# design.net
KiCad netlist of a schematic drawn in Altium Designer
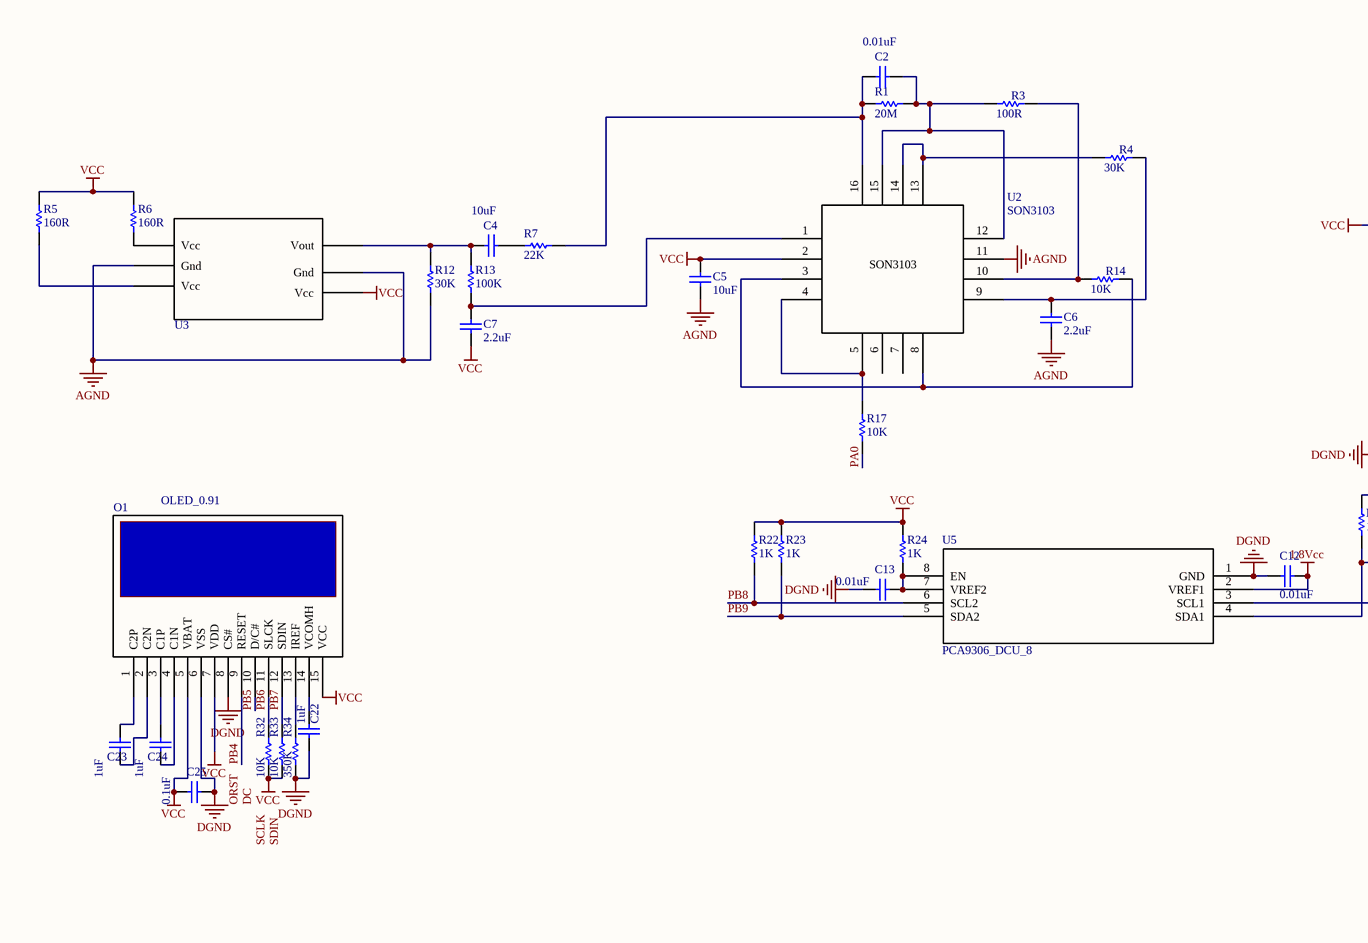
[diagram p0: 手环.SchDoc, left]
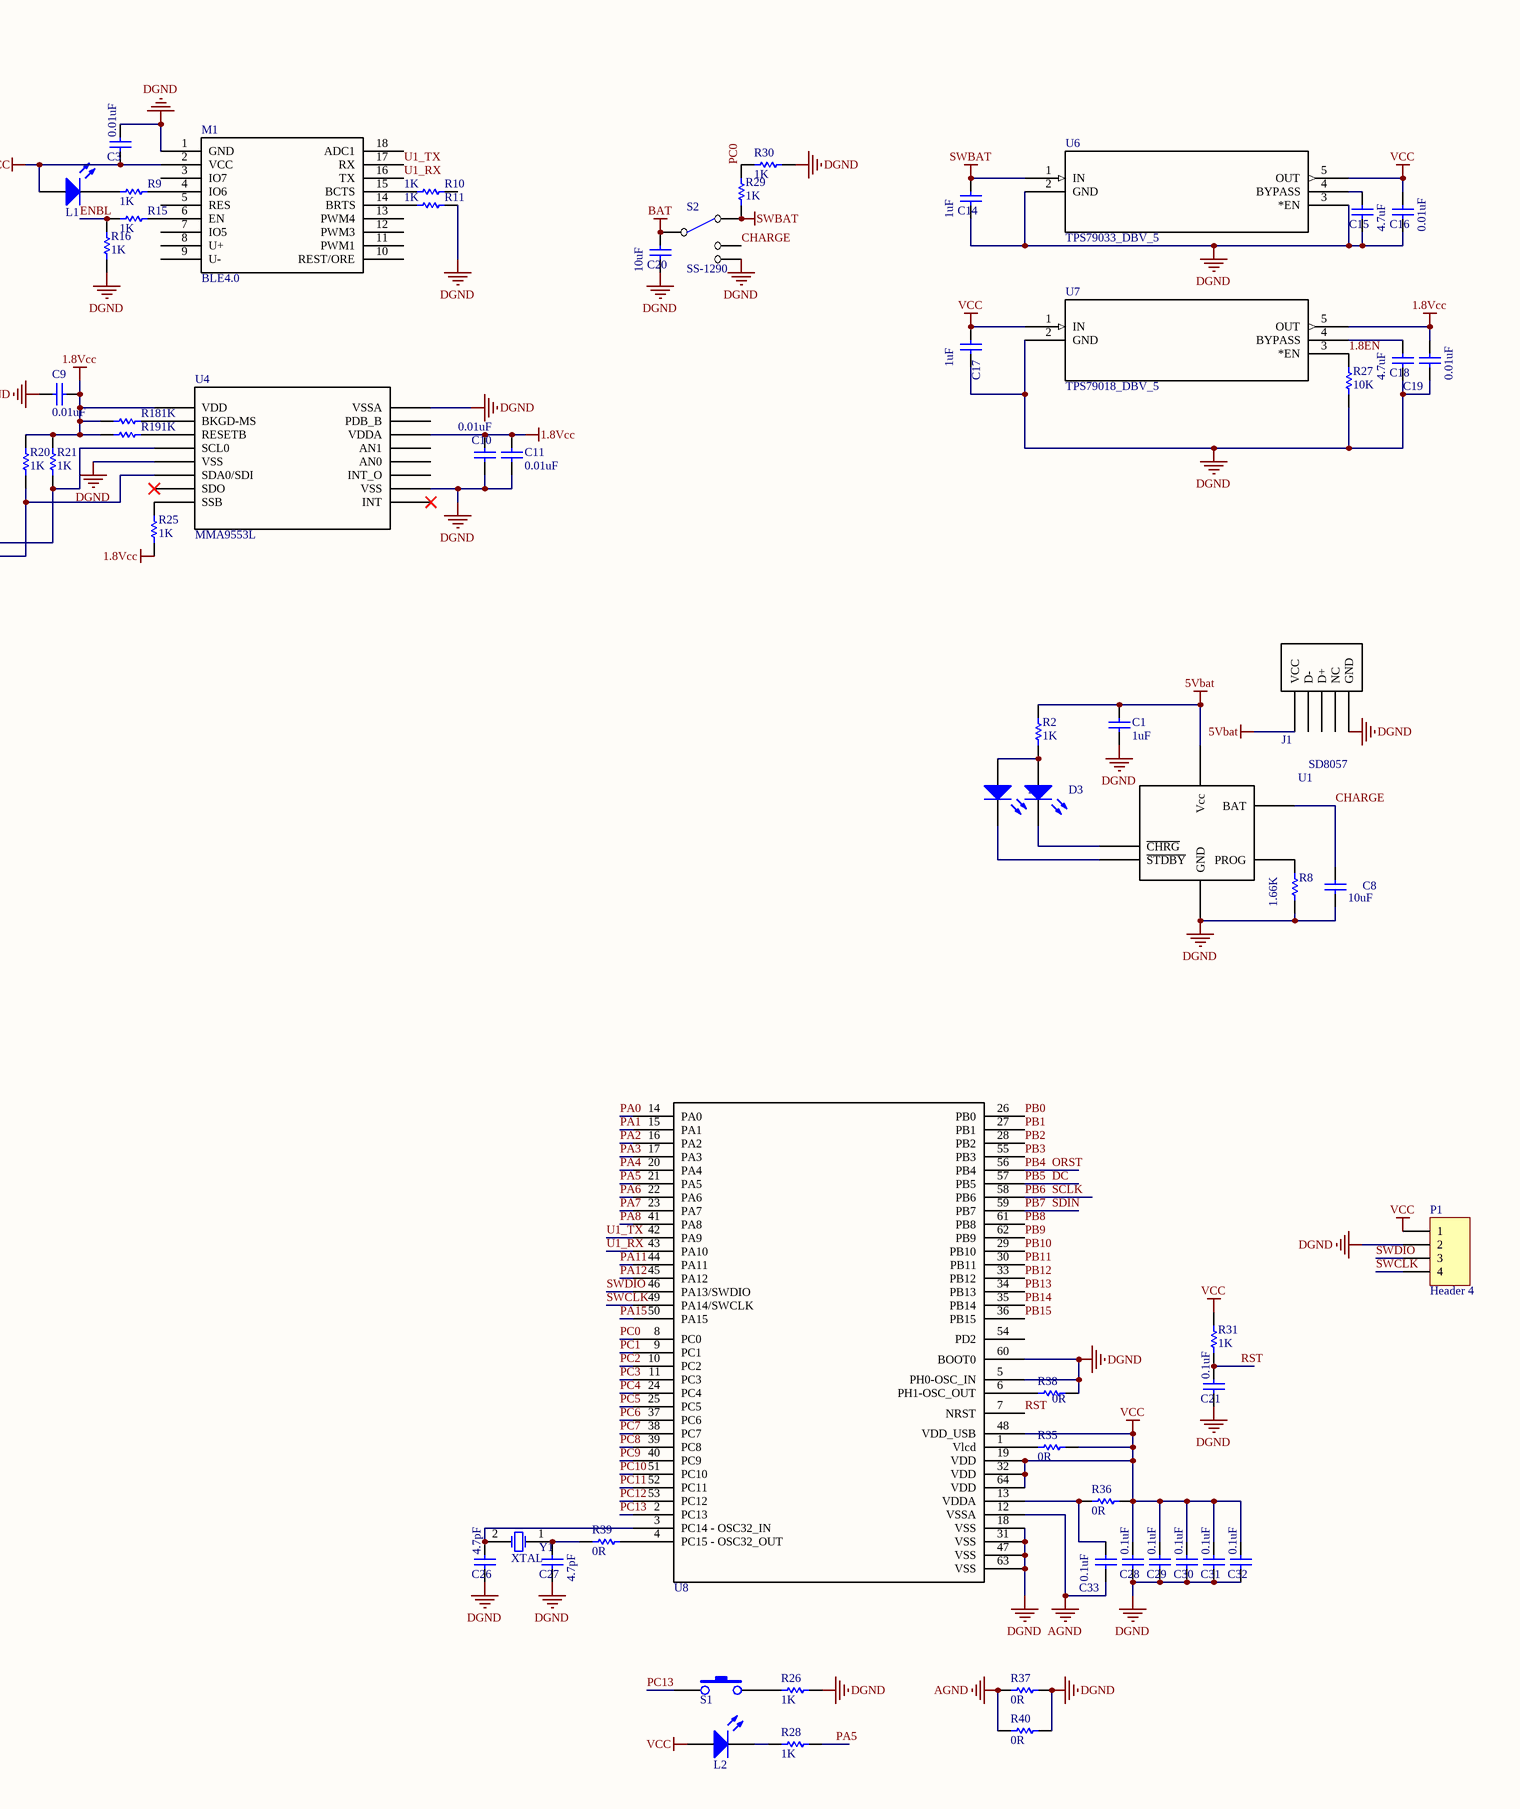
[diagram p1: 手环.SchDoc, right]

(export (version "E")
  (design (tool "Eeschema 10.0.6"))
  (components
    (comp (ref "C1")
      (value "1uF")
      (footprint "0603-C-SMD")
      (description "Capacitor")
      (fields (field (name "Comment") "Cap") (field (name "PUBLISHER") "Altium Limited"))
      (libsource (lib "Miscellaneous Devices") (part "Cap"))
    )
    (comp (ref "C2")
      (value "0.01uF")
      (footprint "0603-c-smd")
      (description "Capacitor")
      (fields (field (name "Comment") "Cap") (field (name "PUBLISHER") "Altium Limited"))
      (libsource (lib "Miscellaneous Devices") (part "Cap"))
    )
    (comp (ref "C3")
      (value "0.01uF")
      (footprint "RAD-0.3")
      (description "Capacitor")
      (fields (field (name "Comment") "Cap") (field (name "PUBLISHER") "Altium Limited"))
      (libsource (lib "Miscellaneous Devices") (part "Cap"))
    )
    (comp (ref "C4")
      (value "10uF")
      (footprint "0603-c-smd")
      (description "Capacitor")
      (fields (field (name "Comment") "Cap") (field (name "PUBLISHER") "Altium Limited"))
      (libsource (lib "Miscellaneous Devices") (part "Cap"))
    )
    (comp (ref "C5")
      (value "10uF")
      (footprint "0603-c-smd")
      (description "Capacitor")
      (fields (field (name "Comment") "Cap") (field (name "PUBLISHER") "Altium Limited"))
      (libsource (lib "Miscellaneous Devices") (part "Cap"))
    )
    (comp (ref "C6")
      (value "2.2uF")
      (footprint "0603-c-smd")
      (description "Capacitor")
      (fields (field (name "Comment") "Cap") (field (name "PUBLISHER") "Altium Limited"))
      (libsource (lib "Miscellaneous Devices") (part "Cap"))
    )
    (comp (ref "C7")
      (value "2.2uF")
      (footprint "0603-c-smd")
      (description "Capacitor")
      (fields (field (name "Comment") "Cap") (field (name "PUBLISHER") "Altium Limited"))
      (libsource (lib "Miscellaneous Devices") (part "Cap"))
    )
    (comp (ref "C8")
      (value "10uF")
      (footprint "0603-C-SMD")
      (description "Capacitor")
      (fields (field (name "Comment") "Cap") (field (name "PUBLISHER") "Altium Limited"))
      (libsource (lib "Miscellaneous Devices") (part "Cap"))
    )
    (comp (ref "C9")
      (value "0.01uF")
      (footprint "RAD-0.3")
      (description "Capacitor")
      (fields (field (name "Comment") "Cap") (field (name "PUBLISHER") "Altium Limited"))
      (libsource (lib "Miscellaneous Devices") (part "Cap"))
    )
    (comp (ref "C10")
      (value "0.01uF")
      (footprint "RAD-0.3")
      (description "Capacitor")
      (fields (field (name "Comment") "Cap") (field (name "PUBLISHER") "Altium Limited"))
      (libsource (lib "Miscellaneous Devices") (part "Cap"))
    )
    (comp (ref "C11")
      (value "0.01uF")
      (footprint "RAD-0.3")
      (description "Capacitor")
      (fields (field (name "Comment") "Cap") (field (name "PUBLISHER") "Altium Limited"))
      (libsource (lib "Miscellaneous Devices") (part "Cap"))
    )
    (comp (ref "C12")
      (value "0.01uF")
      (footprint "RAD-0.3")
      (description "Capacitor")
      (fields (field (name "Comment") "Cap") (field (name "PUBLISHER") "Altium Limited"))
      (libsource (lib "Miscellaneous Devices") (part "Cap"))
    )
    (comp (ref "C13")
      (value "0.01uF")
      (footprint "RAD-0.3")
      (description "Capacitor")
      (fields (field (name "Comment") "Cap") (field (name "PUBLISHER") "Altium Limited"))
      (libsource (lib "Miscellaneous Devices") (part "Cap"))
    )
    (comp (ref "C14")
      (value "1uF")
      (footprint "RAD-0.3")
      (description "Capacitor")
      (fields (field (name "Comment") "Cap") (field (name "PUBLISHER") "Altium Limited"))
      (libsource (lib "Miscellaneous Devices") (part "Cap"))
    )
    (comp (ref "C15")
      (value "4.7uF")
      (footprint "RAD-0.3")
      (description "Capacitor")
      (fields (field (name "Comment") "Cap") (field (name "PUBLISHER") "Altium Limited"))
      (libsource (lib "Miscellaneous Devices") (part "Cap"))
    )
    (comp (ref "C16")
      (value "0.01uF")
      (footprint "RAD-0.3")
      (description "Capacitor")
      (fields (field (name "Comment") "Cap") (field (name "PUBLISHER") "Altium Limited"))
      (libsource (lib "Miscellaneous Devices") (part "Cap"))
    )
    (comp (ref "C17")
      (value "1uF")
      (footprint "RAD-0.3")
      (description "Capacitor")
      (fields (field (name "Comment") "Cap") (field (name "PUBLISHER") "Altium Limited"))
      (libsource (lib "Miscellaneous Devices") (part "Cap"))
    )
    (comp (ref "C18")
      (value "4.7uF")
      (footprint "RAD-0.3")
      (description "Capacitor")
      (fields (field (name "Comment") "Cap") (field (name "PUBLISHER") "Altium Limited"))
      (libsource (lib "Miscellaneous Devices") (part "Cap"))
    )
    (comp (ref "C19")
      (value "0.01uF")
      (footprint "RAD-0.3")
      (description "Capacitor")
      (fields (field (name "Comment") "Cap") (field (name "PUBLISHER") "Altium Limited"))
      (libsource (lib "Miscellaneous Devices") (part "Cap"))
    )
    (comp (ref "C20")
      (value "10uF")
      (footprint "RAD-0.3")
      (description "Capacitor")
      (fields (field (name "Comment") "Cap") (field (name "PUBLISHER") "Altium Limited"))
      (libsource (lib "Miscellaneous Devices") (part "Cap"))
    )
    (comp (ref "C21")
      (value "0.1uF")
      (footprint "RAD-0.3")
      (description "Capacitor")
      (fields (field (name "Comment") "Cap") (field (name "PUBLISHER") "Altium Limited"))
      (libsource (lib "Miscellaneous Devices") (part "Cap"))
    )
    (comp (ref "C22")
      (value "1uF")
      (footprint "RAD-0.3")
      (description "Capacitor")
      (fields (field (name "Comment") "Cap") (field (name "PUBLISHER") "Altium Limited"))
      (libsource (lib "Miscellaneous Devices") (part "Cap"))
    )
    (comp (ref "C23")
      (value "1uF")
      (footprint "RAD-0.3")
      (description "Capacitor")
      (fields (field (name "Comment") "Cap") (field (name "PUBLISHER") "Altium Limited"))
      (libsource (lib "Miscellaneous Devices") (part "Cap"))
    )
    (comp (ref "C24")
      (value "1uF")
      (footprint "RAD-0.3")
      (description "Capacitor")
      (fields (field (name "Comment") "Cap") (field (name "PUBLISHER") "Altium Limited"))
      (libsource (lib "Miscellaneous Devices") (part "Cap"))
    )
    (comp (ref "C25")
      (value "0.1uF")
      (footprint "RAD-0.3")
      (description "Capacitor")
      (fields (field (name "Comment") "Cap") (field (name "PUBLISHER") "Altium Limited"))
      (libsource (lib "Miscellaneous Devices") (part "Cap"))
    )
    (comp (ref "C26")
      (value "4.7pF")
      (footprint "RAD-0.3")
      (description "Capacitor")
      (fields (field (name "Comment") "Cap") (field (name "PUBLISHER") "Altium Limited"))
      (libsource (lib "Miscellaneous Devices") (part "Cap"))
    )
    (comp (ref "C27")
      (value "4.7pF")
      (footprint "RAD-0.3")
      (description "Capacitor")
      (fields (field (name "Comment") "Cap") (field (name "PUBLISHER") "Altium Limited"))
      (libsource (lib "Miscellaneous Devices") (part "Cap"))
    )
    (comp (ref "C28")
      (value "0.1uF")
      (footprint "RAD-0.3")
      (description "Capacitor")
      (fields (field (name "Comment") "Cap") (field (name "PUBLISHER") "Altium Limited"))
      (libsource (lib "Miscellaneous Devices") (part "Cap"))
    )
    (comp (ref "C29")
      (value "0.1uF")
      (footprint "RAD-0.3")
      (description "Capacitor")
      (fields (field (name "Comment") "Cap") (field (name "PUBLISHER") "Altium Limited"))
      (libsource (lib "Miscellaneous Devices") (part "Cap"))
    )
    (comp (ref "C30")
      (value "0.1uF")
      (footprint "RAD-0.3")
      (description "Capacitor")
      (fields (field (name "Comment") "Cap") (field (name "PUBLISHER") "Altium Limited"))
      (libsource (lib "Miscellaneous Devices") (part "Cap"))
    )
    (comp (ref "C31")
      (value "0.1uF")
      (footprint "RAD-0.3")
      (description "Capacitor")
      (fields (field (name "Comment") "Cap") (field (name "PUBLISHER") "Altium Limited"))
      (libsource (lib "Miscellaneous Devices") (part "Cap"))
    )
    (comp (ref "C32")
      (value "0.1uF")
      (footprint "RAD-0.3")
      (description "Capacitor")
      (fields (field (name "Comment") "Cap") (field (name "PUBLISHER") "Altium Limited"))
      (libsource (lib "Miscellaneous Devices") (part "Cap"))
    )
    (comp (ref "C33")
      (value "0.1uF")
      (footprint "RAD-0.3")
      (description "Capacitor")
      (fields (field (name "Comment") "Cap") (field (name "PUBLISHER") "Altium Limited"))
      (libsource (lib "Miscellaneous Devices") (part "Cap"))
    )
    (comp (ref "D2")
      (value "LED0")
      (footprint "LED-0805")
      (description "Typical INFRARED GaAs LED")
      (fields (field (name "PUBLISHER") "Altium Limited"))
      (libsource (lib "Miscellaneous Devices") (part "LED0"))
    )
    (comp (ref "D3")
      (value "LED0")
      (footprint "LED-0805")
      (description "Typical INFRARED GaAs LED")
      (fields (field (name "PUBLISHER") "Altium Limited"))
      (libsource (lib "Miscellaneous Devices") (part "LED0"))
    )
    (comp (ref "J1") (value "USB") (footprint "Micro_USB") (libsource (lib "My Library") (part "micro usb")))
    (comp (ref "L1") (value "LED") (footprint "C2012") (libsource (lib "Sparks") (part "LED")))
    (comp (ref "L2") (value "LED") (footprint "C2012") (libsource (lib "Sparks") (part "LED")))
    (comp (ref "M1") (value "BLE4.0") (footprint "BLE4.0") (libsource (lib "My Library") (part "BLE4.0模块")))
    (comp (ref "O1")
      (value "OLED_0.91")
      (footprint "OLED_0.91")
      (libsource (lib "My Library") (part "OLED-0.91"))
    )
    (comp (ref "P1")
      (value "Header 4")
      (footprint "HDR1X4")
      (description "Header, 4-Pin")
      (fields (field (name "PUBLISHER") "Altium Limited"))
      (libsource (lib "Sparks") (part "Header 4"))
    )
    (comp (ref "R1")
      (value "20M")
      (footprint "R2012")
      (description "贴片电阻")
      (fields (field (name "Comment") "Res") (field (name "PUBLISHER") "Altium Limited"))
      (libsource (lib "Sparks") (part "Res"))
    )
    (comp (ref "R2")
      (value "1K")
      (footprint "0603-R-SMD")
      (description "贴片电阻")
      (fields (field (name "Comment") "Res") (field (name "PUBLISHER") "Altium Limited"))
      (libsource (lib "Sparks") (part "Res"))
    )
    (comp (ref "R3")
      (value "100R")
      (footprint "R2012")
      (description "贴片电阻")
      (fields (field (name "Comment") "Res") (field (name "PUBLISHER") "Altium Limited"))
      (libsource (lib "Sparks") (part "Res"))
    )
    (comp (ref "R4")
      (value "30K")
      (footprint "R2012")
      (description "贴片电阻")
      (fields (field (name "Comment") "Res") (field (name "PUBLISHER") "Altium Limited"))
      (libsource (lib "Sparks") (part "Res"))
    )
    (comp (ref "R5")
      (value "160R")
      (footprint "R2012")
      (description "贴片电阻")
      (fields (field (name "Comment") "Res") (field (name "PUBLISHER") "Altium Limited"))
      (libsource (lib "Sparks") (part "Res"))
    )
    (comp (ref "R6")
      (value "160R")
      (footprint "R2012")
      (description "贴片电阻")
      (fields (field (name "Comment") "Res") (field (name "PUBLISHER") "Altium Limited"))
      (libsource (lib "Sparks") (part "Res"))
    )
    (comp (ref "R7")
      (value "22K")
      (footprint "R2012")
      (description "贴片电阻")
      (fields (field (name "Comment") "Res") (field (name "PUBLISHER") "Altium Limited"))
      (libsource (lib "Sparks") (part "Res"))
    )
    (comp (ref "R8")
      (value "1.66K")
      (footprint "0603-R-SMD")
      (description "贴片电阻")
      (fields (field (name "Comment") "Res") (field (name "PUBLISHER") "Altium Limited"))
      (libsource (lib "Sparks") (part "Res"))
    )
    (comp (ref "R9")
      (value "1K")
      (footprint "R2012")
      (description "贴片电阻")
      (fields (field (name "Comment") "Res") (field (name "PUBLISHER") "Altium Limited"))
      (libsource (lib "Sparks") (part "Res"))
    )
    (comp (ref "R10")
      (value "1K")
      (footprint "R2012")
      (description "贴片电阻")
      (fields (field (name "Comment") "Res") (field (name "PUBLISHER") "Altium Limited"))
      (libsource (lib "Sparks") (part "Res"))
    )
    (comp (ref "R11")
      (value "1K")
      (footprint "R2012")
      (description "贴片电阻")
      (fields (field (name "Comment") "Res") (field (name "PUBLISHER") "Altium Limited"))
      (libsource (lib "Sparks") (part "Res"))
    )
    (comp (ref "R12")
      (value "30K")
      (footprint "R2012")
      (description "贴片电阻")
      (fields (field (name "Comment") "Res") (field (name "PUBLISHER") "Altium Limited"))
      (libsource (lib "Sparks") (part "Res"))
    )
    (comp (ref "R13")
      (value "100K")
      (footprint "R2012")
      (description "贴片电阻")
      (fields (field (name "Comment") "Res") (field (name "PUBLISHER") "Altium Limited"))
      (libsource (lib "Sparks") (part "Res"))
    )
    (comp (ref "R14")
      (value "10K")
      (footprint "R2012")
      (description "贴片电阻")
      (fields (field (name "Comment") "Res") (field (name "PUBLISHER") "Altium Limited"))
      (libsource (lib "Sparks") (part "Res"))
    )
    (comp (ref "R15")
      (value "1K")
      (footprint "R2012")
      (description "贴片电阻")
      (fields (field (name "Comment") "Res") (field (name "PUBLISHER") "Altium Limited"))
      (libsource (lib "Sparks") (part "Res"))
    )
    (comp (ref "R16")
      (value "1K")
      (footprint "R2012")
      (description "贴片电阻")
      (fields (field (name "Comment") "Res") (field (name "PUBLISHER") "Altium Limited"))
      (libsource (lib "Sparks") (part "Res"))
    )
    (comp (ref "R17")
      (value "10K")
      (footprint "R2012")
      (description "贴片电阻")
      (fields (field (name "Comment") "Res") (field (name "PUBLISHER") "Altium Limited"))
      (libsource (lib "Sparks") (part "Res"))
    )
    (comp (ref "R18")
      (value "1K")
      (footprint "R2012")
      (description "贴片电阻")
      (fields (field (name "Comment") "Res") (field (name "PUBLISHER") "Altium Limited"))
      (libsource (lib "Sparks") (part "Res"))
    )
    (comp (ref "R19")
      (value "1K")
      (footprint "R2012")
      (description "贴片电阻")
      (fields (field (name "Comment") "Res") (field (name "PUBLISHER") "Altium Limited"))
      (libsource (lib "Sparks") (part "Res"))
    )
    (comp (ref "R20")
      (value "1K")
      (footprint "R2012")
      (description "贴片电阻")
      (fields (field (name "Comment") "Res") (field (name "PUBLISHER") "Altium Limited"))
      (libsource (lib "Sparks") (part "Res"))
    )
    (comp (ref "R21")
      (value "1K")
      (footprint "R2012")
      (description "贴片电阻")
      (fields (field (name "Comment") "Res") (field (name "PUBLISHER") "Altium Limited"))
      (libsource (lib "Sparks") (part "Res"))
    )
    (comp (ref "R22")
      (value "1K")
      (footprint "R2012")
      (description "贴片电阻")
      (fields (field (name "Comment") "Res") (field (name "PUBLISHER") "Altium Limited"))
      (libsource (lib "Sparks") (part "Res"))
    )
    (comp (ref "R23")
      (value "1K")
      (footprint "R2012")
      (description "贴片电阻")
      (fields (field (name "Comment") "Res") (field (name "PUBLISHER") "Altium Limited"))
      (libsource (lib "Sparks") (part "Res"))
    )
    (comp (ref "R24")
      (value "1K")
      (footprint "R2012")
      (description "贴片电阻")
      (fields (field (name "Comment") "Res") (field (name "PUBLISHER") "Altium Limited"))
      (libsource (lib "Sparks") (part "Res"))
    )
    (comp (ref "R25")
      (value "1K")
      (footprint "R2012")
      (description "贴片电阻")
      (fields (field (name "Comment") "Res") (field (name "PUBLISHER") "Altium Limited"))
      (libsource (lib "Sparks") (part "Res"))
    )
    (comp (ref "R26")
      (value "1K")
      (footprint "R2012")
      (description "贴片电阻")
      (fields (field (name "Comment") "Res") (field (name "PUBLISHER") "Altium Limited"))
      (libsource (lib "Sparks") (part "Res"))
    )
    (comp (ref "R27")
      (value "10K")
      (footprint "R2012")
      (description "贴片电阻")
      (fields (field (name "Comment") "Res") (field (name "PUBLISHER") "Altium Limited"))
      (libsource (lib "Sparks") (part "Res"))
    )
    (comp (ref "R28")
      (value "1K")
      (footprint "R2012")
      (description "贴片电阻")
      (fields (field (name "Comment") "Res") (field (name "PUBLISHER") "Altium Limited"))
      (libsource (lib "Sparks") (part "Res"))
    )
    (comp (ref "R29")
      (value "1K")
      (footprint "R2012")
      (description "贴片电阻")
      (fields (field (name "Comment") "Res") (field (name "PUBLISHER") "Altium Limited"))
      (libsource (lib "Sparks") (part "Res"))
    )
    (comp (ref "R30")
      (value "1K")
      (footprint "R2012")
      (description "贴片电阻")
      (fields (field (name "Comment") "Res") (field (name "PUBLISHER") "Altium Limited"))
      (libsource (lib "Sparks") (part "Res"))
    )
    (comp (ref "R31")
      (value "1K")
      (footprint "R2012")
      (description "贴片电阻")
      (fields (field (name "Comment") "Res") (field (name "PUBLISHER") "Altium Limited"))
      (libsource (lib "Sparks") (part "Res"))
    )
    (comp (ref "R32")
      (value "10K")
      (footprint "R2012")
      (description "贴片电阻")
      (fields (field (name "Comment") "Res") (field (name "PUBLISHER") "Altium Limited"))
      (libsource (lib "Sparks") (part "Res"))
    )
    (comp (ref "R33")
      (value "10K")
      (footprint "R2012")
      (description "贴片电阻")
      (fields (field (name "Comment") "Res") (field (name "PUBLISHER") "Altium Limited"))
      (libsource (lib "Sparks") (part "Res"))
    )
    (comp (ref "R34")
      (value "350K")
      (footprint "R2012")
      (description "贴片电阻")
      (fields (field (name "Comment") "Res") (field (name "PUBLISHER") "Altium Limited"))
      (libsource (lib "Sparks") (part "Res"))
    )
    (comp (ref "R35")
      (value "0R")
      (footprint "R2012")
      (description "贴片电阻")
      (fields (field (name "Comment") "Res") (field (name "PUBLISHER") "Altium Limited"))
      (libsource (lib "Sparks") (part "Res"))
    )
    (comp (ref "R36")
      (value "0R")
      (footprint "R2012")
      (description "贴片电阻")
      (fields (field (name "Comment") "Res") (field (name "PUBLISHER") "Altium Limited"))
      (libsource (lib "Sparks") (part "Res"))
    )
    (comp (ref "R37")
      (value "0R")
      (footprint "R2012")
      (description "贴片电阻")
      (fields (field (name "Comment") "Res") (field (name "PUBLISHER") "Altium Limited"))
      (libsource (lib "Sparks") (part "Res"))
    )
    (comp (ref "R38")
      (value "0R")
      (footprint "R2012")
      (description "贴片电阻")
      (fields (field (name "Comment") "Res") (field (name "PUBLISHER") "Altium Limited"))
      (libsource (lib "Sparks") (part "Res"))
    )
    (comp (ref "R39")
      (value "0R")
      (footprint "R2012")
      (description "贴片电阻")
      (fields (field (name "Comment") "Res") (field (name "PUBLISHER") "Altium Limited"))
      (libsource (lib "Sparks") (part "Res"))
    )
    (comp (ref "R40")
      (value "0R")
      (footprint "R2012")
      (description "贴片电阻")
      (fields (field (name "Comment") "Res") (field (name "PUBLISHER") "Altium Limited"))
      (libsource (lib "Sparks") (part "Res"))
    )
    (comp (ref "S1") (value "微动开关") (footprint "贴片按键") (libsource (lib "开关") (part "微动开关")))
    (comp (ref "S2") (value "SS-1290") (footprint "MSK-1102") (libsource (lib "My Library") (part "SS-1290")))
    (comp (ref "U1") (value "SD8057") (footprint "SOT-23-6") (libsource (lib "My Library") (part "SD8057")))
    (comp (ref "U2")
      (value "SON3103")
      (footprint "TQFN-3*3-16L")
      (libsource (lib "My Library") (part "son3103"))
    )
    (comp (ref "U3") (value "SON1303") (footprint "SON1303") (libsource (lib "My Library") (part "SON1303")))
    (comp (ref "U4")
      (value "MMA9553L")
      (footprint "QFN127P600-8N")
      (libsource (lib "My Library") (part "MMA9553L"))
    )
    (comp (ref "U5")
      (value "PCA9306_DCU_8")
      (footprint "DCT8")
      (description "Imported")
      (fields
        (field (name "MANUFACTURER") "Texas Instruments")
        (field (name "GENERIC_PART_NUMBER") "PCA9306")
      )
      (libsource (lib "My Library") (part "PCA9306_DCU_8"))
    )
    (comp (ref "U6")
      (value "TPS79033_DBV_5")
      (footprint "DBV5")
      (description "Imported")
      (fields
        (field (name "MANUFACTURER_PART_NUMBER") "tps79018_dbv_5")
        (field (name "GENERIC_PART_NUMBER") "TPS79018")
      )
      (libsource (lib "My Library") (part "TPS79018_DBV_5"))
    )
    (comp (ref "U7")
      (value "TPS79018_DBV_5")
      (footprint "DBV5")
      (description "Imported")
      (fields
        (field (name "MANUFACTURER_PART_NUMBER") "tps79018_dbv_5")
        (field (name "GENERIC_PART_NUMBER") "TPS79018")
      )
      (libsource (lib "My Library") (part "TPS79018_DBV_5"))
    )
    (comp (ref "U8")
      (value "STM32L05xx")
      (footprint "QFP127P600-8N")
      (libsource (lib "My Library") (part "STM32L05xx"))
    )
    (comp (ref "Y1")
      (value "XTAL")
      (footprint "XTAL-B")
      (description "晶体振荡器")
      (fields (field (name "PUBLISHER") "Altium Limited"))
      (libsource (lib "Sparks") (part "XTAL"))
    )
  )
  (nets
    (net (code "1") (name "/1.8EN") (class "Default")
      (node (ref "R27") (pin "1") (pinfunction "1_1") (pintype "passive"))
      (node (ref "U7") (pin "3") (pinfunction "*EN_3") (pintype "passive"))
    )
    (net (code "2") (name "/CHARGE") (class "Default")
      (node (ref "C8") (pin "2") (pinfunction "2_2") (pintype "passive"))
      (node (ref "S2") (pin "3") (pinfunction "NO_3") (pintype "passive"))
      (node (ref "U1") (pin "3") (pinfunction "BAT_3") (pintype "passive"))
    )
    (net (code "3") (name "/DC") (class "Default")
      (node (ref "O1") (pin "10") (pinfunction "D/C#_10") (pintype "passive"))
      (node (ref "U8") (pin "57") (pinfunction "PB5_57") (pintype "passive"))
    )
    (net (code "4") (name "/ENBL") (class "Default")
      (node (ref "R15") (pin "1") (pinfunction "1_1") (pintype "passive"))
      (node (ref "R16") (pin "2") (pinfunction "2_2") (pintype "passive"))
    )
    (net (code "5") (name "/ORST") (class "Default")
      (node (ref "O1") (pin "9") (pinfunction "RESET_9") (pintype "passive"))
      (node (ref "U8") (pin "56") (pinfunction "PB4_56") (pintype "passive"))
    )
    (net (code "6") (name "/PA0") (class "Default")
      (node (ref "R17") (pin "2") (pinfunction "2_2") (pintype "passive"))
      (node (ref "U8") (pin "14") (pinfunction "PA0_14") (pintype "passive"))
    )
    (net (code "7") (name "/PA1") (class "Default")
      (node (ref "U8") (pin "15") (pinfunction "PA1_15") (pintype "passive"))
    )
    (net (code "8") (name "/PA2") (class "Default")
      (node (ref "U8") (pin "16") (pinfunction "PA2_16") (pintype "passive"))
    )
    (net (code "9") (name "/PA3") (class "Default")
      (node (ref "U8") (pin "17") (pinfunction "PA3_17") (pintype "passive"))
    )
    (net (code "10") (name "/PA4") (class "Default")
      (node (ref "U8") (pin "20") (pinfunction "PA4_20") (pintype "passive"))
    )
    (net (code "11") (name "/PA5") (class "Default")
      (node (ref "R28") (pin "2") (pinfunction "2_2") (pintype "passive"))
      (node (ref "U8") (pin "21") (pinfunction "PA5_21") (pintype "passive"))
    )
    (net (code "12") (name "/PA6") (class "Default")
      (node (ref "U8") (pin "22") (pinfunction "PA6_22") (pintype "passive"))
    )
    (net (code "13") (name "/PA7") (class "Default")
      (node (ref "U8") (pin "23") (pinfunction "PA7_23") (pintype "passive"))
    )
    (net (code "14") (name "/PA8") (class "Default")
      (node (ref "U8") (pin "41") (pinfunction "PA8_41") (pintype "passive"))
    )
    (net (code "15") (name "/PA11") (class "Default")
      (node (ref "U8") (pin "44") (pinfunction "PA11_44") (pintype "passive"))
    )
    (net (code "16") (name "/PA12") (class "Default")
      (node (ref "U8") (pin "45") (pinfunction "PA12_45") (pintype "passive"))
    )
    (net (code "17") (name "/PA15") (class "Default")
      (node (ref "U8") (pin "50") (pinfunction "PA15_50") (pintype "passive"))
    )
    (net (code "18") (name "/PB0") (class "Default")
      (node (ref "U8") (pin "26") (pinfunction "PB0_26") (pintype "passive"))
    )
    (net (code "19") (name "/PB1") (class "Default")
      (node (ref "U8") (pin "27") (pinfunction "PB1_27") (pintype "passive"))
    )
    (net (code "20") (name "/PB2") (class "Default")
      (node (ref "U8") (pin "28") (pinfunction "PB2_28") (pintype "passive"))
    )
    (net (code "21") (name "/PB3") (class "Default")
      (node (ref "U8") (pin "55") (pinfunction "PB3_55") (pintype "passive"))
    )
    (net (code "22") (name "/PB6") (class "Default")
      (node (ref "O1") (pin "11") (pinfunction "SLCK_11") (pintype "passive"))
      (node (ref "R32") (pin "2") (pinfunction "2_2") (pintype "passive"))
      (node (ref "U8") (pin "58") (pinfunction "PB6_58") (pintype "passive"))
    )
    (net (code "23") (name "/PB7") (class "Default")
      (node (ref "O1") (pin "12") (pinfunction "SDIN_12") (pintype "passive"))
      (node (ref "R33") (pin "2") (pinfunction "2_2") (pintype "passive"))
      (node (ref "U8") (pin "59") (pinfunction "PB7_59") (pintype "passive"))
    )
    (net (code "24") (name "/PB8") (class "Default")
      (node (ref "R22") (pin "1") (pinfunction "1_1") (pintype "passive"))
      (node (ref "U5") (pin "6") (pinfunction "SCL2_6") (pintype "passive"))
      (node (ref "U8") (pin "61") (pinfunction "PB8_61") (pintype "passive"))
    )
    (net (code "25") (name "/PB9") (class "Default")
      (node (ref "R23") (pin "1") (pinfunction "1_1") (pintype "passive"))
      (node (ref "U5") (pin "5") (pinfunction "SDA2_5") (pintype "passive"))
      (node (ref "U8") (pin "62") (pinfunction "PB9_62") (pintype "passive"))
    )
    (net (code "26") (name "/PB10") (class "Default")
      (node (ref "U8") (pin "29") (pinfunction "PB10_29") (pintype "passive"))
    )
    (net (code "27") (name "/PB11") (class "Default")
      (node (ref "U8") (pin "30") (pinfunction "PB11_30") (pintype "passive"))
    )
    (net (code "28") (name "/PB12") (class "Default")
      (node (ref "U8") (pin "33") (pinfunction "PB12_33") (pintype "passive"))
    )
    (net (code "29") (name "/PB13") (class "Default")
      (node (ref "U8") (pin "34") (pinfunction "PB13_34") (pintype "passive"))
    )
    (net (code "30") (name "/PB14") (class "Default")
      (node (ref "U8") (pin "35") (pinfunction "PB14_35") (pintype "passive"))
    )
    (net (code "31") (name "/PB15") (class "Default")
      (node (ref "U8") (pin "36") (pinfunction "PB15_36") (pintype "passive"))
    )
    (net (code "32") (name "/PC0") (class "Default")
      (node (ref "R29") (pin "2") (pinfunction "2_2") (pintype "passive"))
      (node (ref "R30") (pin "2") (pinfunction "2_2") (pintype "passive"))
      (node (ref "U8") (pin "8") (pinfunction "PC0_8") (pintype "passive"))
    )
    (net (code "33") (name "/PC1") (class "Default")
      (node (ref "U8") (pin "9") (pinfunction "PC1_9") (pintype "passive"))
    )
    (net (code "34") (name "/PC2") (class "Default")
      (node (ref "U8") (pin "10") (pinfunction "PC2_10") (pintype "passive"))
    )
    (net (code "35") (name "/PC3") (class "Default")
      (node (ref "U8") (pin "11") (pinfunction "PC3_11") (pintype "passive"))
    )
    (net (code "36") (name "/PC4") (class "Default")
      (node (ref "U8") (pin "24") (pinfunction "PC4_24") (pintype "passive"))
    )
    (net (code "37") (name "/PC5") (class "Default")
      (node (ref "U8") (pin "25") (pinfunction "PC5_25") (pintype "passive"))
    )
    (net (code "38") (name "/PC6") (class "Default")
      (node (ref "U8") (pin "37") (pinfunction "PC6_37") (pintype "passive"))
    )
    (net (code "39") (name "/PC7") (class "Default")
      (node (ref "U8") (pin "38") (pinfunction "PC7_38") (pintype "passive"))
    )
    (net (code "40") (name "/PC8") (class "Default")
      (node (ref "U8") (pin "39") (pinfunction "PC8_39") (pintype "passive"))
    )
    (net (code "41") (name "/PC9") (class "Default")
      (node (ref "U8") (pin "40") (pinfunction "PC9_40") (pintype "passive"))
    )
    (net (code "42") (name "/PC10") (class "Default")
      (node (ref "U8") (pin "51") (pinfunction "PC10_51") (pintype "passive"))
    )
    (net (code "43") (name "/PC11") (class "Default")
      (node (ref "U8") (pin "52") (pinfunction "PC11_52") (pintype "passive"))
    )
    (net (code "44") (name "/PC12") (class "Default")
      (node (ref "U8") (pin "53") (pinfunction "PC12_53") (pintype "passive"))
    )
    (net (code "45") (name "/PC13") (class "Default")
      (node (ref "S1") (pin "1") (pinfunction "1_1") (pintype "passive"))
      (node (ref "U8") (pin "2") (pinfunction "PC13_2") (pintype "passive"))
    )
    (net (code "46") (name "/RST") (class "Default")
      (node (ref "C21") (pin "2") (pinfunction "2_2") (pintype "passive"))
      (node (ref "R31") (pin "1") (pinfunction "1_1") (pintype "passive"))
      (node (ref "U8") (pin "7") (pinfunction "NRST_7") (pintype "passive"))
    )
    (net (code "47") (name "/SWCLK") (class "Default")
      (node (ref "P1") (pin "4") (pinfunction "4_4") (pintype "passive"))
      (node (ref "U8") (pin "49") (pinfunction "PA14/SWCLK_49") (pintype "passive"))
    )
    (net (code "48") (name "/SWDIO") (class "Default")
      (node (ref "P1") (pin "3") (pinfunction "3_3") (pintype "passive"))
      (node (ref "U8") (pin "46") (pinfunction "PA13/SWDIO_46") (pintype "passive"))
    )
    (net (code "49") (name "/U1_RX") (class "Default")
      (node (ref "M1") (pin "16") (pinfunction "TX_16") (pintype "passive"))
      (node (ref "U8") (pin "43") (pinfunction "PA10_43") (pintype "passive"))
    )
    (net (code "50") (name "/U1_TX") (class "Default")
      (node (ref "M1") (pin "17") (pinfunction "RX_17") (pintype "passive"))
      (node (ref "U8") (pin "42") (pinfunction "PA9_42") (pintype "passive"))
    )
    (net (code "51") (name "1.8Vcc") (class "Default")
      (node (ref "C10") (pin "1") (pinfunction "1_1") (pintype "passive"))
      (node (ref "C11") (pin "1") (pinfunction "1_1") (pintype "passive"))
      (node (ref "C12") (pin "1") (pinfunction "1_1") (pintype "passive"))
      (node (ref "C19") (pin "2") (pinfunction "2_2") (pintype "passive"))
      (node (ref "C9") (pin "1") (pinfunction "1_1") (pintype "passive"))
      (node (ref "R18") (pin "1") (pinfunction "1_1") (pintype "passive"))
      (node (ref "R19") (pin "1") (pinfunction "1_1") (pintype "passive"))
      (node (ref "R20") (pin "2") (pinfunction "2_2") (pintype "passive"))
      (node (ref "R21") (pin "2") (pinfunction "2_2") (pintype "passive"))
      (node (ref "R25") (pin "1") (pinfunction "1_1") (pintype "passive"))
      (node (ref "U4") (pin "1") (pinfunction "VDD_1") (pintype "passive"))
      (node (ref "U4") (pin "14") (pinfunction "VDDA_14") (pintype "passive"))
      (node (ref "U5") (pin "2") (pinfunction "VREF1_2") (pintype "power_in"))
      (node (ref "U7") (pin "5") (pinfunction "OUT_5") (pintype "output"))
    )
    (net (code "52") (name "5Vbat") (class "Default")
      (node (ref "C1") (pin "2") (pinfunction "2_2") (pintype "passive"))
      (node (ref "J1") (pin "5") (pinfunction "VCC_5") (pintype "passive"))
      (node (ref "R2") (pin "2") (pinfunction "2_2") (pintype "passive"))
      (node (ref "U1") (pin "4") (pinfunction "Vcc_4") (pintype "passive"))
    )
    (net (code "53") (name "AGND") (class "Default")
      (node (ref "C33") (pin "1") (pinfunction "1_1") (pintype "passive"))
      (node (ref "C5") (pin "1") (pinfunction "1_1") (pintype "passive"))
      (node (ref "C6") (pin "1") (pinfunction "1_1") (pintype "passive"))
      (node (ref "R12") (pin "2") (pinfunction "2_2") (pintype "passive"))
      (node (ref "R37") (pin "1") (pinfunction "1_1") (pintype "passive"))
      (node (ref "R40") (pin "1") (pinfunction "1_1") (pintype "passive"))
      (node (ref "U2") (pin "11") (pinfunction "11_11") (pintype "passive"))
      (node (ref "U3") (pin "2") (pinfunction "Gnd_2") (pintype "passive"))
      (node (ref "U3") (pin "5") (pinfunction "Gnd_5") (pintype "passive"))
      (node (ref "U8") (pin "12") (pinfunction "VSSA_12") (pintype "passive"))
    )
    (net (code "54") (name "BAT") (class "Default")
      (node (ref "C20") (pin "2") (pinfunction "2_2") (pintype "passive"))
      (node (ref "S2") (pin "2") (pinfunction "COMMON_2") (pintype "passive"))
    )
    (net (code "55") (name "DGND") (class "Default")
      (node (ref "C1") (pin "1") (pinfunction "1_1") (pintype "passive"))
      (node (ref "C10") (pin "2") (pinfunction "2_2") (pintype "passive"))
      (node (ref "C11") (pin "2") (pinfunction "2_2") (pintype "passive"))
      (node (ref "C12") (pin "2") (pinfunction "2_2") (pintype "passive"))
      (node (ref "C13") (pin "2") (pinfunction "2_2") (pintype "passive"))
      (node (ref "C14") (pin "1") (pinfunction "1_1") (pintype "passive"))
      (node (ref "C15") (pin "1") (pinfunction "1_1") (pintype "passive"))
      (node (ref "C16") (pin "1") (pinfunction "1_1") (pintype "passive"))
      (node (ref "C17") (pin "1") (pinfunction "1_1") (pintype "passive"))
      (node (ref "C18") (pin "1") (pinfunction "1_1") (pintype "passive"))
      (node (ref "C19") (pin "1") (pinfunction "1_1") (pintype "passive"))
      (node (ref "C20") (pin "1") (pinfunction "1_1") (pintype "passive"))
      (node (ref "C21") (pin "1") (pinfunction "1_1") (pintype "passive"))
      (node (ref "C22") (pin "1") (pinfunction "1_1") (pintype "passive"))
      (node (ref "C25") (pin "1") (pinfunction "1_1") (pintype "passive"))
      (node (ref "C26") (pin "1") (pinfunction "1_1") (pintype "passive"))
      (node (ref "C27") (pin "1") (pinfunction "1_1") (pintype "passive"))
      (node (ref "C28") (pin "1") (pinfunction "1_1") (pintype "passive"))
      (node (ref "C29") (pin "1") (pinfunction "1_1") (pintype "passive"))
      (node (ref "C3") (pin "2") (pinfunction "2_2") (pintype "passive"))
      (node (ref "C30") (pin "1") (pinfunction "1_1") (pintype "passive"))
      (node (ref "C31") (pin "1") (pinfunction "1_1") (pintype "passive"))
      (node (ref "C32") (pin "1") (pinfunction "1_1") (pintype "passive"))
      (node (ref "C8") (pin "1") (pinfunction "1_1") (pintype "passive"))
      (node (ref "C9") (pin "2") (pinfunction "2_2") (pintype "passive"))
      (node (ref "J1") (pin "1") (pinfunction "GND_1") (pintype "passive"))
      (node (ref "M1") (pin "1") (pinfunction "GND_1") (pintype "passive"))
      (node (ref "O1") (pin "6") (pinfunction "VSS_6") (pintype "passive"))
      (node (ref "O1") (pin "8") (pinfunction "CS#_8") (pintype "passive"))
      (node (ref "P1") (pin "2") (pinfunction "2_2") (pintype "passive"))
      (node (ref "R11") (pin "2") (pinfunction "2_2") (pintype "passive"))
      (node (ref "R16") (pin "1") (pinfunction "1_1") (pintype "passive"))
      (node (ref "R26") (pin "2") (pinfunction "2_2") (pintype "passive"))
      (node (ref "R27") (pin "2") (pinfunction "2_2") (pintype "passive"))
      (node (ref "R30") (pin "1") (pinfunction "1_1") (pintype "passive"))
      (node (ref "R34") (pin "1") (pinfunction "1_1") (pintype "passive"))
      (node (ref "R37") (pin "2") (pinfunction "2_2") (pintype "passive"))
      (node (ref "R38") (pin "2") (pinfunction "2_2") (pintype "passive"))
      (node (ref "R40") (pin "2") (pinfunction "2_2") (pintype "passive"))
      (node (ref "R8") (pin "1") (pinfunction "1_1") (pintype "passive"))
      (node (ref "S2") (pin "0") (pinfunction "G_0") (pintype "passive"))
      (node (ref "U1") (pin "2") (pinfunction "GND_2") (pintype "passive"))
      (node (ref "U4") (pin "10") (pinfunction "VSS_10") (pintype "passive"))
      (node (ref "U4") (pin "16") (pinfunction "VSSA_16") (pintype "passive"))
      (node (ref "U4") (pin "5") (pinfunction "VSS_5") (pintype "passive"))
      (node (ref "U5") (pin "1") (pinfunction "GND_1") (pintype "power_in"))
      (node (ref "U6") (pin "2") (pinfunction "GND_2") (pintype "power_in"))
      (node (ref "U6") (pin "3") (pinfunction "*EN_3") (pintype "passive"))
      (node (ref "U7") (pin "2") (pinfunction "GND_2") (pintype "power_in"))
      (node (ref "U8") (pin "18") (pinfunction "VSS_18") (pintype "passive"))
      (node (ref "U8") (pin "31") (pinfunction "VSS_31") (pintype "passive"))
      (node (ref "U8") (pin "47") (pinfunction "VSS_47") (pintype "passive"))
      (node (ref "U8") (pin "5") (pinfunction "PH0-OSC_IN_5") (pintype "passive"))
      (node (ref "U8") (pin "60") (pinfunction "BOOT0_60") (pintype "passive"))
      (node (ref "U8") (pin "63") (pinfunction "VSS_63") (pintype "passive"))
    )
    (net (code "56") (name "Net-(C2-Pad1)") (class "Default")
      (node (ref "C2") (pin "1") (pinfunction "1_1") (pintype "passive"))
      (node (ref "R1") (pin "2") (pinfunction "2_2") (pintype "passive"))
      (node (ref "R7") (pin "2") (pinfunction "2_2") (pintype "passive"))
      (node (ref "U2") (pin "16") (pinfunction "16_16") (pintype "passive"))
    )
    (net (code "57") (name "Net-(C2-Pad2)") (class "Default")
      (node (ref "C2") (pin "2") (pinfunction "2_2") (pintype "passive"))
      (node (ref "R1") (pin "1") (pinfunction "1_1") (pintype "passive"))
      (node (ref "R3") (pin "2") (pinfunction "2_2") (pintype "passive"))
      (node (ref "U2") (pin "12") (pinfunction "12_12") (pintype "passive"))
      (node (ref "U2") (pin "15") (pinfunction "15_15") (pintype "passive"))
    )
    (net (code "58") (name "Net-(C4-Pad2)") (class "Default")
      (node (ref "C4") (pin "2") (pinfunction "2_2") (pintype "passive"))
      (node (ref "R7") (pin "1") (pinfunction "1_1") (pintype "passive"))
    )
    (net (code "59") (name "Net-(C6-Pad2)") (class "Default")
      (node (ref "C6") (pin "2") (pinfunction "2_2") (pintype "passive"))
      (node (ref "R4") (pin "1") (pinfunction "1_1") (pintype "passive"))
      (node (ref "U2") (pin "9") (pinfunction "9_9") (pintype "passive"))
    )
    (net (code "60") (name "Net-(C7-Pad2)") (class "Default")
      (node (ref "C7") (pin "2") (pinfunction "2_2") (pintype "passive"))
      (node (ref "R13") (pin "2") (pinfunction "2_2") (pintype "passive"))
      (node (ref "U2") (pin "1") (pinfunction "1_1") (pintype "passive"))
    )
    (net (code "61") (name "Net-(D2-A)") (class "Default")
      (node (ref "D2") (pin "1") (pinfunction "A_1") (pintype "passive"))
      (node (ref "D3") (pin "1") (pinfunction "A_1") (pintype "passive"))
      (node (ref "R2") (pin "1") (pinfunction "1_1") (pintype "passive"))
    )
    (net (code "62") (name "Net-(D2-K)") (class "Default")
      (node (ref "D2") (pin "2") (pinfunction "K_2") (pintype "passive"))
      (node (ref "U1") (pin "5") (pinfunction "~{STDBY}_5") (pintype "passive"))
    )
    (net (code "63") (name "Net-(D3-K)") (class "Default")
      (node (ref "D3") (pin "2") (pinfunction "K_2") (pintype "passive"))
      (node (ref "U1") (pin "1") (pinfunction "~{CHRG}_1") (pintype "passive"))
    )
    (net (code "64") (name "Net-(L1-K)") (class "Default")
      (node (ref "L1") (pin "2") (pinfunction "K_2") (pintype "passive"))
      (node (ref "R9") (pin "1") (pinfunction "1_1") (pintype "passive"))
    )
    (net (code "65") (name "Net-(L2-K)") (class "Default")
      (node (ref "L2") (pin "2") (pinfunction "K_2") (pintype "passive"))
      (node (ref "R28") (pin "1") (pinfunction "1_1") (pintype "passive"))
    )
    (net (code "66") (name "Net-(M1-BCTS)") (class "Default")
      (node (ref "M1") (pin "15") (pinfunction "BCTS_15") (pintype "passive"))
      (node (ref "R10") (pin "1") (pinfunction "1_1") (pintype "passive"))
    )
    (net (code "67") (name "Net-(M1-BRTS)") (class "Default")
      (node (ref "M1") (pin "14") (pinfunction "BRTS_14") (pintype "passive"))
      (node (ref "R11") (pin "1") (pinfunction "1_1") (pintype "passive"))
    )
    (net (code "68") (name "Net-(M1-EN)") (class "Default")
      (node (ref "M1") (pin "6") (pinfunction "EN_6") (pintype "passive"))
      (node (ref "R15") (pin "2") (pinfunction "2_2") (pintype "passive"))
    )
    (net (code "69") (name "Net-(M1-IO6)") (class "Default")
      (node (ref "M1") (pin "4") (pinfunction "IO6_4") (pintype "passive"))
      (node (ref "R9") (pin "2") (pinfunction "2_2") (pintype "passive"))
    )
    (net (code "70") (name "Net-(O1-C1N)") (class "Default")
      (node (ref "C24") (pin "1") (pinfunction "1_1") (pintype "passive"))
      (node (ref "O1") (pin "4") (pinfunction "C1N_4") (pintype "passive"))
    )
    (net (code "71") (name "Net-(O1-C1P)") (class "Default")
      (node (ref "C24") (pin "2") (pinfunction "2_2") (pintype "passive"))
      (node (ref "O1") (pin "3") (pinfunction "C1P_3") (pintype "passive"))
    )
    (net (code "72") (name "Net-(O1-C2N)") (class "Default")
      (node (ref "C23") (pin "1") (pinfunction "1_1") (pintype "passive"))
      (node (ref "O1") (pin "2") (pinfunction "C2N_2") (pintype "passive"))
    )
    (net (code "73") (name "Net-(O1-C2P)") (class "Default")
      (node (ref "C23") (pin "2") (pinfunction "2_2") (pintype "passive"))
      (node (ref "O1") (pin "1") (pinfunction "C2P_1") (pintype "passive"))
    )
    (net (code "74") (name "Net-(O1-IREF)") (class "Default")
      (node (ref "O1") (pin "13") (pinfunction "IREF_13") (pintype "passive"))
      (node (ref "R34") (pin "2") (pinfunction "2_2") (pintype "passive"))
    )
    (net (code "75") (name "Net-(O1-VCOMH)") (class "Default")
      (node (ref "C22") (pin "2") (pinfunction "2_2") (pintype "passive"))
      (node (ref "O1") (pin "14") (pinfunction "VCOMH_14") (pintype "passive"))
    )
    (net (code "76") (name "Net-(R4-Pad2)") (class "Default")
      (node (ref "R4") (pin "2") (pinfunction "2_2") (pintype "passive"))
      (node (ref "U2") (pin "13") (pinfunction "13_13") (pintype "passive"))
      (node (ref "U2") (pin "14") (pinfunction "14_14") (pintype "passive"))
    )
    (net (code "77") (name "Net-(R5-Pad1)") (class "Default")
      (node (ref "R5") (pin "1") (pinfunction "1_1") (pintype "passive"))
      (node (ref "U3") (pin "3") (pinfunction "Vcc_3") (pintype "passive"))
    )
    (net (code "78") (name "Net-(R6-Pad2)") (class "Default")
      (node (ref "R6") (pin "2") (pinfunction "2_2") (pintype "passive"))
      (node (ref "U3") (pin "1") (pinfunction "Vcc_1") (pintype "passive"))
    )
    (net (code "79") (name "Net-(R14-Pad1)") (class "Default")
      (node (ref "R14") (pin "1") (pinfunction "1_1") (pintype "passive"))
      (node (ref "U2") (pin "3") (pinfunction "3_3") (pintype "passive"))
      (node (ref "U2") (pin "8") (pinfunction "8_8") (pintype "passive"))
    )
    (net (code "80") (name "Net-(R14-Pad2)") (class "Default")
      (node (ref "R14") (pin "2") (pinfunction "2_2") (pintype "passive"))
      (node (ref "R3") (pin "1") (pinfunction "1_1") (pintype "passive"))
      (node (ref "U2") (pin "10") (pinfunction "10_10") (pintype "passive"))
    )
    (net (code "81") (name "Net-(R17-Pad1)") (class "Default")
      (node (ref "R17") (pin "1") (pinfunction "1_1") (pintype "passive"))
      (node (ref "U2") (pin "4") (pinfunction "4_4") (pintype "passive"))
      (node (ref "U2") (pin "5") (pinfunction "5_5") (pintype "passive"))
    )
    (net (code "82") (name "Net-(R26-Pad1)") (class "Default")
      (node (ref "R26") (pin "1") (pinfunction "1_1") (pintype "passive"))
      (node (ref "S1") (pin "2") (pinfunction "2_2") (pintype "passive"))
    )
    (net (code "83") (name "Net-(U1-PROG)") (class "Default")
      (node (ref "R8") (pin "2") (pinfunction "2_2") (pintype "passive"))
      (node (ref "U1") (pin "6") (pinfunction "PROG_6") (pintype "passive"))
    )
    (net (code "84") (name "Net-(U3-Vout)") (class "Default")
      (node (ref "C4") (pin "1") (pinfunction "1_1") (pintype "passive"))
      (node (ref "R12") (pin "1") (pinfunction "1_1") (pintype "passive"))
      (node (ref "R13") (pin "1") (pinfunction "1_1") (pintype "passive"))
      (node (ref "U3") (pin "6") (pinfunction "Vout_6") (pintype "passive"))
    )
    (net (code "85") (name "Net-(U4-BKGD-MS)") (class "Default")
      (node (ref "R18") (pin "2") (pinfunction "2_2") (pintype "passive"))
      (node (ref "U4") (pin "2") (pinfunction "BKGD-MS_2") (pintype "passive"))
    )
    (net (code "86") (name "Net-(U4-RESETB)") (class "Default")
      (node (ref "R19") (pin "2") (pinfunction "2_2") (pintype "passive"))
      (node (ref "U4") (pin "3") (pinfunction "RESETB_3") (pintype "passive"))
    )
    (net (code "87") (name "Net-(U4-SCL0)") (class "Default")
      (node (ref "R21") (pin "1") (pinfunction "1_1") (pintype "passive"))
      (node (ref "U4") (pin "4") (pinfunction "SCL0_4") (pintype "passive"))
      (node (ref "U5") (pin "3") (pinfunction "SCL1_3") (pintype "passive"))
    )
    (net (code "88") (name "Net-(U4-SDA0{slash}SDI)") (class "Default")
      (node (ref "R20") (pin "1") (pinfunction "1_1") (pintype "passive"))
      (node (ref "U4") (pin "6") (pinfunction "SDA0/SDI_6") (pintype "passive"))
      (node (ref "U5") (pin "4") (pinfunction "SDA1_4") (pintype "passive"))
    )
    (net (code "89") (name "Net-(U4-SSB)") (class "Default")
      (node (ref "R25") (pin "2") (pinfunction "2_2") (pintype "passive"))
      (node (ref "U4") (pin "8") (pinfunction "SSB_8") (pintype "passive"))
    )
    (net (code "90") (name "Net-(U5-EN)") (class "Default")
      (node (ref "C13") (pin "1") (pinfunction "1_1") (pintype "passive"))
      (node (ref "R24") (pin "1") (pinfunction "1_1") (pintype "passive"))
      (node (ref "U5") (pin "7") (pinfunction "VREF2_7") (pintype "power_in"))
      (node (ref "U5") (pin "8") (pinfunction "EN_8") (pintype "passive"))
    )
    (net (code "91") (name "Net-(U6-BYPASS)") (class "Default")
      (node (ref "C15") (pin "2") (pinfunction "2_2") (pintype "passive"))
      (node (ref "U6") (pin "4") (pinfunction "BYPASS_4") (pintype "passive"))
    )
    (net (code "92") (name "Net-(U7-BYPASS)") (class "Default")
      (node (ref "C18") (pin "2") (pinfunction "2_2") (pintype "passive"))
      (node (ref "U7") (pin "4") (pinfunction "BYPASS_4") (pintype "passive"))
    )
    (net (code "93") (name "Net-(U8-PC14_-_OSC32_IN)") (class "Default")
      (node (ref "C26") (pin "2") (pinfunction "2_2") (pintype "passive"))
      (node (ref "U8") (pin "3") (pinfunction "PC14_-_OSC32_IN_3") (pintype "passive"))
      (node (ref "Y1") (pin "2") (pinfunction "OSC2_2") (pintype "passive"))
    )
    (net (code "94") (name "Net-(U8-PC15_-_OSC32_OUT)") (class "Default")
      (node (ref "R39") (pin "2") (pinfunction "2_2") (pintype "passive"))
      (node (ref "U8") (pin "4") (pinfunction "PC15_-_OSC32_OUT_4") (pintype "passive"))
    )
    (net (code "95") (name "Net-(U8-PH1-OSC_OUT)") (class "Default")
      (node (ref "R38") (pin "1") (pinfunction "1_1") (pintype "passive"))
      (node (ref "U8") (pin "6") (pinfunction "PH1-OSC_OUT_6") (pintype "passive"))
    )
    (net (code "96") (name "Net-(U8-VDDA)") (class "Default")
      (node (ref "C33") (pin "2") (pinfunction "2_2") (pintype "passive"))
      (node (ref "R36") (pin "1") (pinfunction "1_1") (pintype "passive"))
      (node (ref "U8") (pin "13") (pinfunction "VDDA_13") (pintype "passive"))
    )
    (net (code "97") (name "Net-(U8-Vlcd)") (class "Default")
      (node (ref "R35") (pin "1") (pinfunction "1_1") (pintype "passive"))
      (node (ref "U8") (pin "1") (pinfunction "Vlcd_1") (pintype "passive"))
    )
    (net (code "98") (name "Net-(Y1-OSC1)") (class "Default")
      (node (ref "C27") (pin "2") (pinfunction "2_2") (pintype "passive"))
      (node (ref "R39") (pin "1") (pinfunction "1_1") (pintype "passive"))
      (node (ref "Y1") (pin "1") (pinfunction "OSC1_1") (pintype "passive"))
    )
    (net (code "99") (name "SWBAT") (class "Default")
      (node (ref "C14") (pin "2") (pinfunction "2_2") (pintype "passive"))
      (node (ref "R29") (pin "1") (pinfunction "1_1") (pintype "passive"))
      (node (ref "S2") (pin "1") (pinfunction "NC_1") (pintype "passive"))
      (node (ref "U6") (pin "1") (pinfunction "IN_1") (pintype "input"))
    )
    (net (code "100") (name "VCC") (class "Default")
      (node (ref "C16") (pin "2") (pinfunction "2_2") (pintype "passive"))
      (node (ref "C17") (pin "2") (pinfunction "2_2") (pintype "passive"))
      (node (ref "C25") (pin "2") (pinfunction "2_2") (pintype "passive"))
      (node (ref "C28") (pin "2") (pinfunction "2_2") (pintype "passive"))
      (node (ref "C29") (pin "2") (pinfunction "2_2") (pintype "passive"))
      (node (ref "C3") (pin "1") (pinfunction "1_1") (pintype "passive"))
      (node (ref "C30") (pin "2") (pinfunction "2_2") (pintype "passive"))
      (node (ref "C31") (pin "2") (pinfunction "2_2") (pintype "passive"))
      (node (ref "C32") (pin "2") (pinfunction "2_2") (pintype "passive"))
      (node (ref "C5") (pin "2") (pinfunction "2_2") (pintype "passive"))
      (node (ref "C7") (pin "1") (pinfunction "1_1") (pintype "passive"))
      (node (ref "L1") (pin "1") (pinfunction "A_1") (pintype "passive"))
      (node (ref "L2") (pin "1") (pinfunction "A_1") (pintype "passive"))
      (node (ref "M1") (pin "2") (pinfunction "VCC_2") (pintype "passive"))
      (node (ref "O1") (pin "15") (pinfunction "VCC_15") (pintype "passive"))
      (node (ref "O1") (pin "5") (pinfunction "VBAT_5") (pintype "passive"))
      (node (ref "O1") (pin "7") (pinfunction "VDD_7") (pintype "passive"))
      (node (ref "P1") (pin "1") (pinfunction "1_1") (pintype "passive"))
      (node (ref "R22") (pin "2") (pinfunction "2_2") (pintype "passive"))
      (node (ref "R23") (pin "2") (pinfunction "2_2") (pintype "passive"))
      (node (ref "R24") (pin "2") (pinfunction "2_2") (pintype "passive"))
      (node (ref "R31") (pin "2") (pinfunction "2_2") (pintype "passive"))
      (node (ref "R32") (pin "1") (pinfunction "1_1") (pintype "passive"))
      (node (ref "R33") (pin "1") (pinfunction "1_1") (pintype "passive"))
      (node (ref "R35") (pin "2") (pinfunction "2_2") (pintype "passive"))
      (node (ref "R36") (pin "2") (pinfunction "2_2") (pintype "passive"))
      (node (ref "R5") (pin "2") (pinfunction "2_2") (pintype "passive"))
      (node (ref "R6") (pin "1") (pinfunction "1_1") (pintype "passive"))
      (node (ref "U2") (pin "2") (pinfunction "2_2") (pintype "passive"))
      (node (ref "U3") (pin "4") (pinfunction "Vcc_4") (pintype "passive"))
      (node (ref "U6") (pin "5") (pinfunction "OUT_5") (pintype "output"))
      (node (ref "U7") (pin "1") (pinfunction "IN_1") (pintype "input"))
      (node (ref "U8") (pin "19") (pinfunction "VDD_19") (pintype "passive"))
      (node (ref "U8") (pin "32") (pinfunction "VDD_32") (pintype "passive"))
      (node (ref "U8") (pin "48") (pinfunction "VDD_USB_48") (pintype "passive"))
      (node (ref "U8") (pin "64") (pinfunction "VDD_64") (pintype "passive"))
    )
    (net (code "101") (name "unconnected-(J1-D+-Pad3)") (class "Default")
      (node (ref "J1") (pin "3") (pinfunction "D+_3") (pintype "passive"))
    )
    (net (code "102") (name "unconnected-(J1-D--Pad4)") (class "Default")
      (node (ref "J1") (pin "4") (pinfunction "D-_4") (pintype "passive"))
    )
    (net (code "103") (name "unconnected-(J1-NC-Pad2)") (class "Default")
      (node (ref "J1") (pin "2") (pinfunction "NC_2") (pintype "passive"))
    )
    (net (code "104") (name "unconnected-(M1-ADC1-Pad18)") (class "Default")
      (node (ref "M1") (pin "18") (pinfunction "ADC1_18") (pintype "passive"))
    )
    (net (code "105") (name "unconnected-(M1-IO5-Pad7)") (class "Default")
      (node (ref "M1") (pin "7") (pinfunction "IO5_7") (pintype "passive"))
    )
    (net (code "106") (name "unconnected-(M1-IO7-Pad3)") (class "Default")
      (node (ref "M1") (pin "3") (pinfunction "IO7_3") (pintype "passive"))
    )
    (net (code "107") (name "unconnected-(M1-PWM1-Pad11)") (class "Default")
      (node (ref "M1") (pin "11") (pinfunction "PWM1_11") (pintype "passive"))
    )
    (net (code "108") (name "unconnected-(M1-PWM3-Pad12)") (class "Default")
      (node (ref "M1") (pin "12") (pinfunction "PWM3_12") (pintype "passive"))
    )
    (net (code "109") (name "unconnected-(M1-PWM4-Pad13)") (class "Default")
      (node (ref "M1") (pin "13") (pinfunction "PWM4_13") (pintype "passive"))
    )
    (net (code "110") (name "unconnected-(M1-RES-Pad5)") (class "Default")
      (node (ref "M1") (pin "5") (pinfunction "RES_5") (pintype "passive"))
    )
    (net (code "111") (name "unconnected-(M1-REST{slash}ORE-Pad10)") (class "Default")
      (node (ref "M1") (pin "10") (pinfunction "REST/ORE_10") (pintype "passive"))
    )
    (net (code "112") (name "unconnected-(M1-U+-Pad8)") (class "Default")
      (node (ref "M1") (pin "8") (pinfunction "U+_8") (pintype "passive"))
    )
    (net (code "113") (name "unconnected-(M1-U--Pad9)") (class "Default")
      (node (ref "M1") (pin "9") (pinfunction "U-_9") (pintype "passive"))
    )
    (net (code "114") (name "unconnected-(R10-Pad2)") (class "Default")
      (node (ref "R10") (pin "2") (pinfunction "2_2") (pintype "passive"))
    )
    (net (code "115") (name "unconnected-(U2-Pad6)") (class "Default")
      (node (ref "U2") (pin "6") (pinfunction "6_6") (pintype "passive"))
    )
    (net (code "116") (name "unconnected-(U2-Pad7)") (class "Default")
      (node (ref "U2") (pin "7") (pinfunction "7_7") (pintype "passive"))
    )
    (net (code "117") (name "unconnected-(U4-AN0-Pad12)") (class "Default")
      (node (ref "U4") (pin "12") (pinfunction "AN0_12") (pintype "passive"))
    )
    (net (code "118") (name "unconnected-(U4-AN1-Pad13)") (class "Default")
      (node (ref "U4") (pin "13") (pinfunction "AN1_13") (pintype "passive"))
    )
    (net (code "119") (name "unconnected-(U4-INT-Pad9)") (class "Default")
      (node (ref "U4") (pin "9") (pinfunction "INT_9") (pintype "passive+no_connect"))
    )
    (net (code "120") (name "unconnected-(U4-INT_O-Pad11)") (class "Default")
      (node (ref "U4") (pin "11") (pinfunction "INT_O_11") (pintype "passive"))
    )
    (net (code "121") (name "unconnected-(U4-PDB_B-Pad15)") (class "Default")
      (node (ref "U4") (pin "15") (pinfunction "PDB_B_15") (pintype "passive"))
    )
    (net (code "122") (name "unconnected-(U4-SDO-Pad7)") (class "Default")
      (node (ref "U4") (pin "7") (pinfunction "SDO_7") (pintype "passive+no_connect"))
    )
    (net (code "123") (name "unconnected-(U8-PD2-Pad54)") (class "Default")
      (node (ref "U8") (pin "54") (pinfunction "PD2_54") (pintype "passive"))
    )
  )
)
